# SchV1.net
KiCad netlist of a schematic drawn in Altium Designer
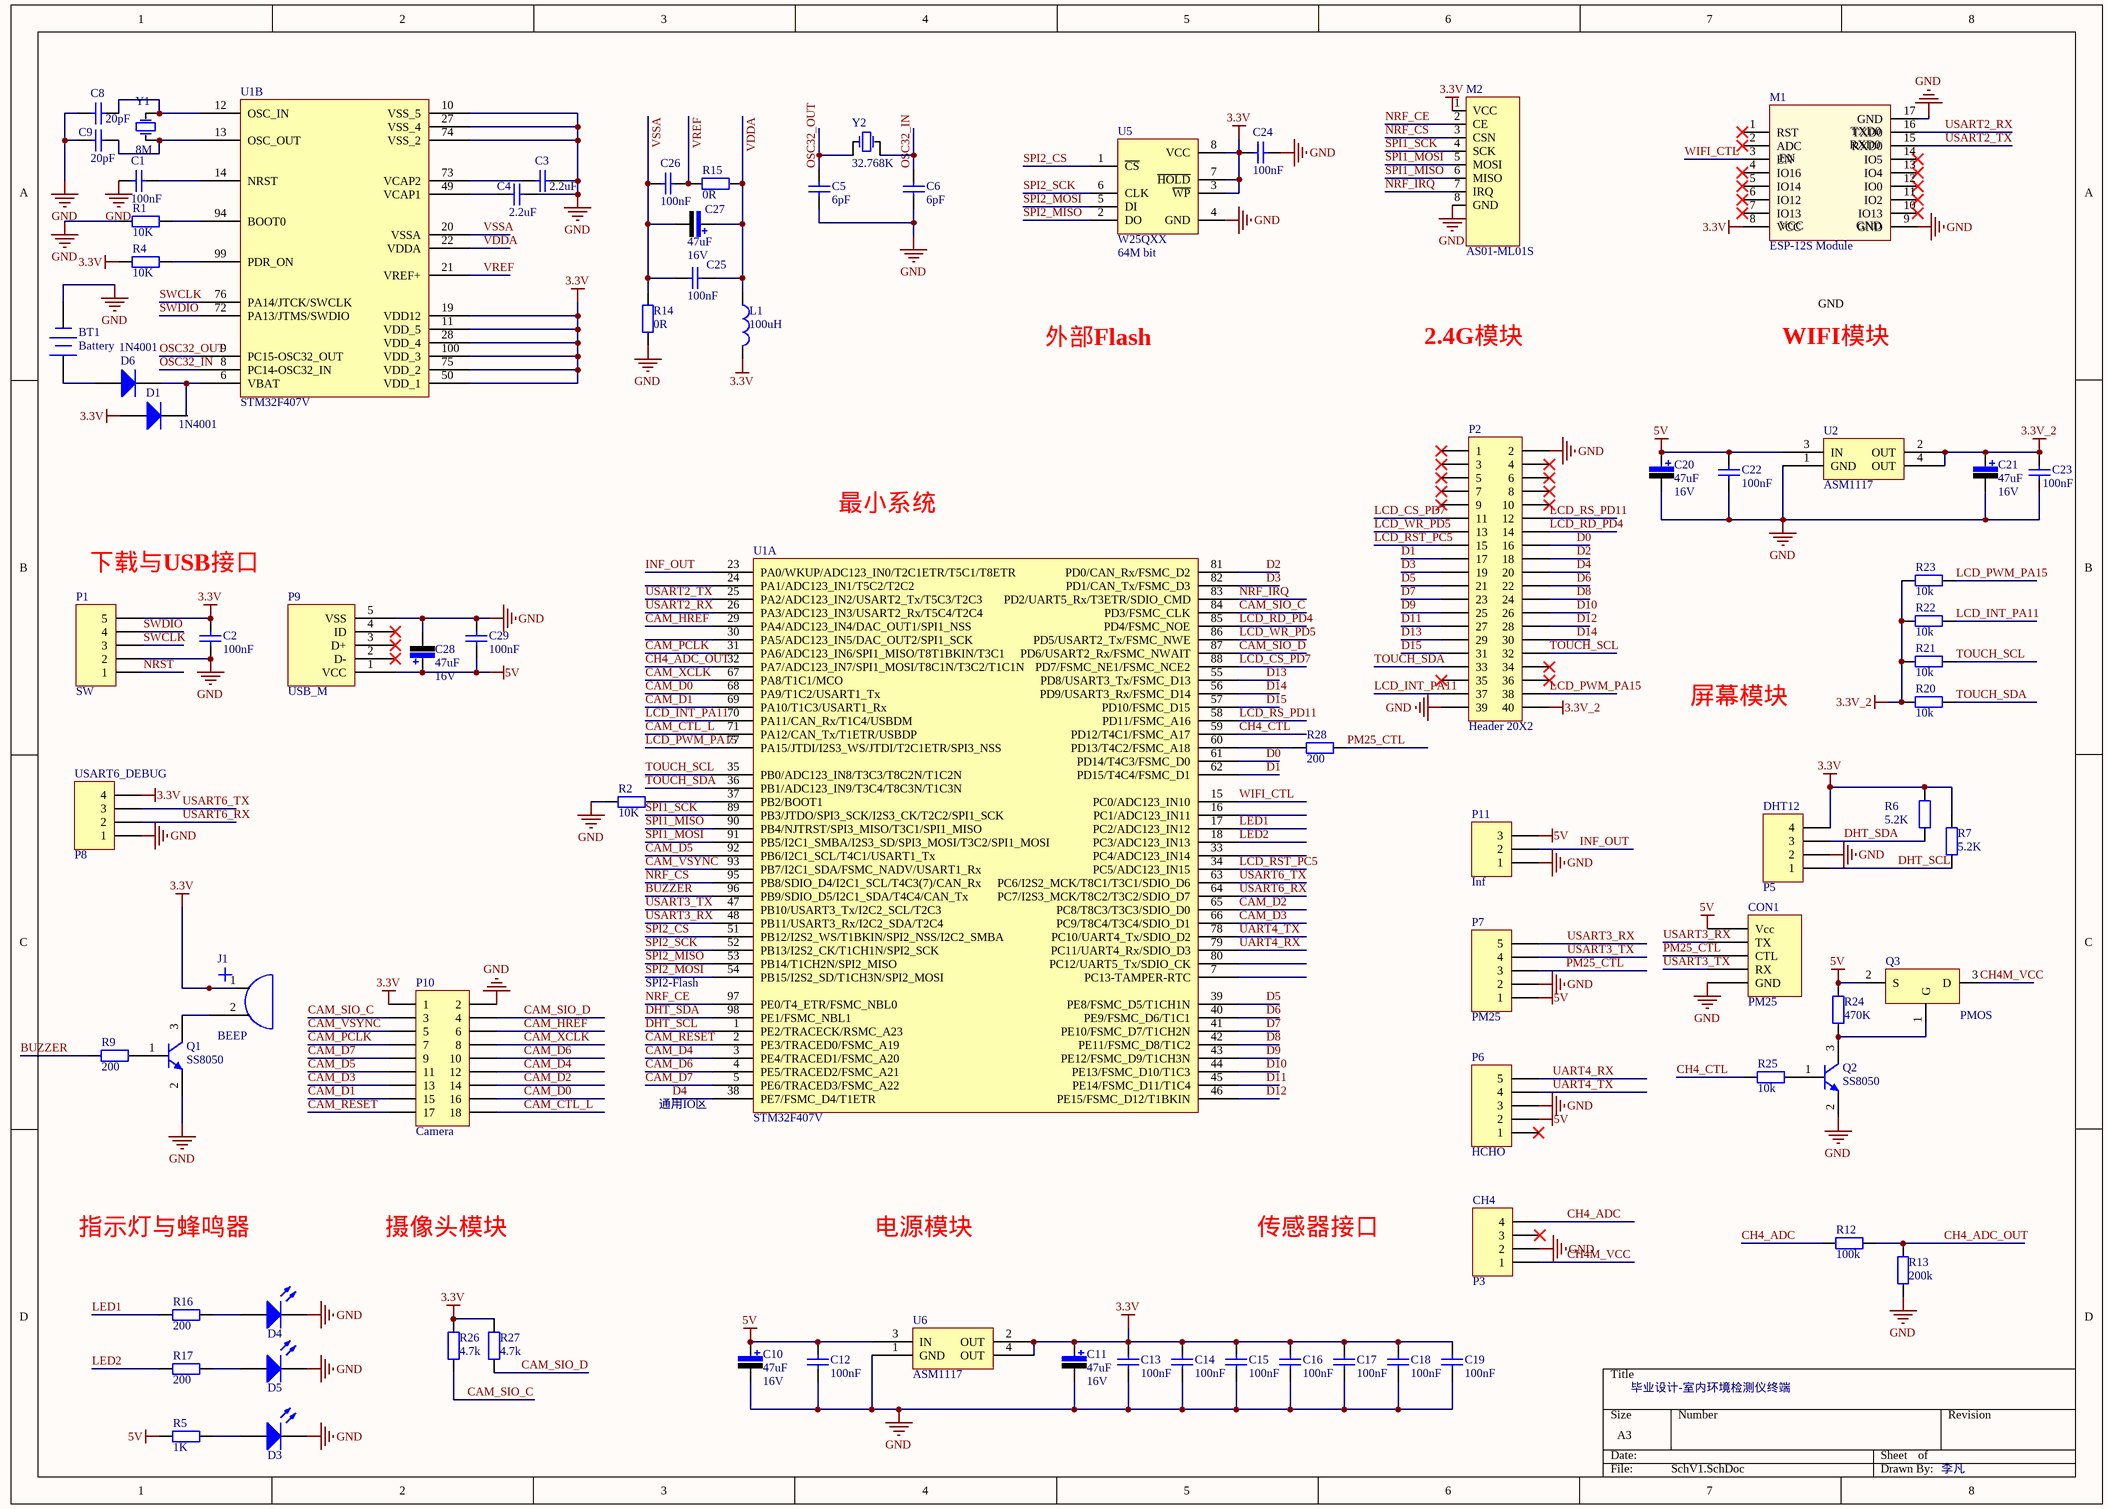
[diagram p0: SchV1.SchDoc]

(export (version "E")
  (design (tool "Eeschema 10.0.6"))
  (components
    (comp (ref "BT1")
      (value "Battery")
      (footprint "CR1220")
      (description "备份电池")
      (libsource (lib "Fszhang") (part "Battery"))
    )
    (comp (ref "C1")
      (value "100nF")
      (footprint "C-RAD-0603")
      (description "无极性电容")
      (fields (field (name "Comment") "Cap"))
      (libsource (lib "Fszhang") (part "Cap"))
    )
    (comp (ref "C2")
      (value "100nF")
      (footprint "C-RAD-0603")
      (description "无极性电容")
      (fields (field (name "Comment") "Cap"))
      (libsource (lib "Fszhang") (part "Cap"))
    )
    (comp (ref "C3")
      (value "2.2uF")
      (footprint "C-RAD-0603")
      (description "无极性电容")
      (fields (field (name "Comment") "Cap"))
      (libsource (lib "Fszhang") (part "Cap"))
    )
    (comp (ref "C4")
      (value "2.2uF")
      (footprint "C-RAD-0603")
      (description "无极性电容")
      (fields (field (name "Comment") "Cap"))
      (libsource (lib "Fszhang") (part "Cap"))
    )
    (comp (ref "C5")
      (value "6pF")
      (footprint "C-RAD-0603")
      (description "无极性电容")
      (fields (field (name "Comment") "Cap"))
      (libsource (lib "Fszhang") (part "Cap"))
    )
    (comp (ref "C6")
      (value "6pF")
      (footprint "C-RAD-0603")
      (description "无极性电容")
      (fields (field (name "Comment") "Cap"))
      (libsource (lib "Fszhang") (part "Cap"))
    )
    (comp (ref "C8")
      (value "20pF")
      (footprint "C-RAD-0603")
      (description "无极性电容")
      (fields (field (name "Comment") "Cap"))
      (libsource (lib "Fszhang") (part "Cap"))
    )
    (comp (ref "C9")
      (value "20pF")
      (footprint "C-RAD-0603")
      (description "无极性电容")
      (fields (field (name "Comment") "Cap"))
      (libsource (lib "Fszhang") (part "Cap"))
    )
    (comp (ref "C10")
      (value "47uF")
      (footprint "CAP-3528")
      (description "极性电解电容")
      (fields (field (name "VOL") "16V") (field (name "Comment") "Cap Pol"))
      (libsource (lib "") (part "Cap Pol_1"))
    )
    (comp (ref "C11")
      (value "47uF")
      (footprint "CAP-3528")
      (description "极性电解电容")
      (fields (field (name "VOL") "16V") (field (name "Comment") "Cap Pol"))
      (libsource (lib "") (part "Cap Pol_1"))
    )
    (comp (ref "C12")
      (value "100nF")
      (footprint "C-RAD-0603")
      (description "无极性电容")
      (fields (field (name "Comment") "Cap"))
      (libsource (lib "Fszhang") (part "Cap"))
    )
    (comp (ref "C13")
      (value "100nF")
      (footprint "C-RAD-0603")
      (description "无极性电容")
      (fields (field (name "Comment") "Cap"))
      (libsource (lib "Fszhang") (part "Cap"))
    )
    (comp (ref "C14")
      (value "100nF")
      (footprint "C-RAD-0603")
      (description "无极性电容")
      (fields (field (name "Comment") "Cap"))
      (libsource (lib "Fszhang") (part "Cap"))
    )
    (comp (ref "C15")
      (value "100nF")
      (footprint "C-RAD-0603")
      (description "无极性电容")
      (fields (field (name "Comment") "Cap"))
      (libsource (lib "Fszhang") (part "Cap"))
    )
    (comp (ref "C16")
      (value "100nF")
      (footprint "C-RAD-0603")
      (description "无极性电容")
      (fields (field (name "Comment") "Cap"))
      (libsource (lib "Fszhang") (part "Cap"))
    )
    (comp (ref "C17")
      (value "100nF")
      (footprint "C-RAD-0603")
      (description "无极性电容")
      (fields (field (name "Comment") "Cap"))
      (libsource (lib "Fszhang") (part "Cap"))
    )
    (comp (ref "C18")
      (value "100nF")
      (footprint "C-RAD-0603")
      (description "无极性电容")
      (fields (field (name "Comment") "Cap"))
      (libsource (lib "Fszhang") (part "Cap"))
    )
    (comp (ref "C19")
      (value "100nF")
      (footprint "C-RAD-0603")
      (description "无极性电容")
      (fields (field (name "Comment") "Cap"))
      (libsource (lib "Fszhang") (part "Cap"))
    )
    (comp (ref "C20")
      (value "47uF")
      (footprint "CAP-3528")
      (description "极性电解电容")
      (fields (field (name "VOL") "16V") (field (name "Comment") "Cap Pol"))
      (libsource (lib "") (part "Cap Pol_1"))
    )
    (comp (ref "C21")
      (value "47uF")
      (footprint "CAP-3528")
      (description "极性电解电容")
      (fields (field (name "VOL") "16V") (field (name "Comment") "Cap Pol"))
      (libsource (lib "") (part "Cap Pol_1"))
    )
    (comp (ref "C22")
      (value "100nF")
      (footprint "C-RAD-0603")
      (description "无极性电容")
      (fields (field (name "Comment") "Cap"))
      (libsource (lib "Fszhang") (part "Cap"))
    )
    (comp (ref "C23")
      (value "100nF")
      (footprint "C-RAD-0603")
      (description "无极性电容")
      (fields (field (name "Comment") "Cap"))
      (libsource (lib "Fszhang") (part "Cap"))
    )
    (comp (ref "C24")
      (value "100nF")
      (footprint "C-RAD-0603")
      (description "无极性电容")
      (fields (field (name "Comment") "Cap"))
      (libsource (lib "Fszhang") (part "Cap"))
    )
    (comp (ref "C25")
      (value "100nF")
      (footprint "C-RAD-0603")
      (description "无极性电容")
      (fields (field (name "Comment") "Cap"))
      (libsource (lib "Fszhang") (part "Cap"))
    )
    (comp (ref "C26")
      (value "100nF")
      (footprint "C-RAD-0603")
      (description "无极性电容")
      (fields (field (name "Comment") "Cap"))
      (libsource (lib "Fszhang") (part "Cap"))
    )
    (comp (ref "C27")
      (value "47uF")
      (footprint "CAP-3528")
      (description "极性电解电容")
      (fields (field (name "VOL") "16V") (field (name "Comment") "Cap Pol"))
      (libsource (lib "Fszhang") (part "Cap Pol"))
    )
    (comp (ref "C28")
      (value "47uF")
      (footprint "CAP-3528")
      (description "极性电解电容")
      (fields (field (name "VOL") "16V") (field (name "Comment") "Cap Pol"))
      (libsource (lib "") (part "Cap Pol_2"))
    )
    (comp (ref "C29")
      (value "100nF")
      (footprint "C-RAD-0603")
      (description "无极性电容")
      (fields (field (name "Comment") "Cap"))
      (libsource (lib "Fszhang") (part "Cap"))
    )
    (comp (ref "CON1") (value "PM25") (libsource (lib "Schlib") (part "USART_sensor")))
    (comp (ref "D1")
      (value "Diode")
      (footprint "DIODE-1206")
      (description "二极管")
      (fields (field (name "TYPE") "1N4001"))
      (libsource (lib "Fszhang") (part "Diode"))
    )
    (comp (ref "D3")
      (value "LED0")
      (footprint "LED_0805")
      (description "发光二极管")
      (libsource (lib "Fszhang") (part "LED0"))
    )
    (comp (ref "D4")
      (value "LED0")
      (footprint "LED_0805")
      (description "发光二极管")
      (libsource (lib "Fszhang") (part "LED0"))
    )
    (comp (ref "D5")
      (value "LED0")
      (footprint "LED_0805")
      (description "发光二极管")
      (libsource (lib "Fszhang") (part "LED0"))
    )
    (comp (ref "D6")
      (value "Diode")
      (footprint "DIODE-1206")
      (description "二极管")
      (fields (field (name "TYPE") "1N4001"))
      (libsource (lib "Fszhang") (part "Diode"))
    )
    (comp (ref "J1")
      (value "BEEP")
      (footprint "Beep")
      (description "蜂鸣器")
      (libsource (lib "Fszhang") (part "BEEP"))
    )
    (comp (ref "L1")
      (value "100uH")
      (footprint "0805-1")
      (description "电感")
      (fields (field (name "Comment") "Inductor"))
      (libsource (lib "Fszhang") (part "Inductor"))
    )
    (comp (ref "M1")
      (value "ESP-12S Module")
      (footprint "ESP-12S Module")
      (libsource (lib "ESP-12S Module") (part "ESP-12S Module"))
    )
    (comp (ref "M2")
      (value "AS01-ML01S")
      (footprint "FanliPcbLib:AS01-ML01S")
      (description "贴片2.4G模块")
      (libsource (lib "Schlib") (part "AS01-ML01S"))
    )
    (comp (ref "P1")
      (value "SW")
      (footprint "FanliPcbLib:7-Header_7mm")
      (description "Header, 5-Pin")
      (libsource (lib "Miscellaneous Connectors") (part "Header 5"))
    )
    (comp (ref "P2")
      (value "Header 20X2")
      (footprint "HDR2X20")
      (description "Header, 20-Pin, Dual row")
      (libsource (lib "Miscellaneous Connectors") (part "Header 20X2"))
    )
    (comp (ref "P3")
      (value "CH4")
      (footprint "HDR4X1_A")
      (description "接插件")
      (libsource (lib "Fszhang") (part "Header 4"))
    )
    (comp (ref "P5")
      (value "DHT12")
      (footprint "HDR4X1_A")
      (description "接插件")
      (libsource (lib "Fszhang") (part "Header 4"))
    )
    (comp (ref "P6")
      (value "HCHO")
      (footprint "7-Header_7mm")
      (description "Header, 5-Pin")
      (libsource (lib "Miscellaneous Connectors") (part "Header 5"))
    )
    (comp (ref "P7")
      (value "PM25")
      (footprint "7-Header_7mm")
      (description "Header, 5-Pin")
      (libsource (lib "Miscellaneous Connectors") (part "Header 5"))
    )
    (comp (ref "P8")
      (value "USART6_DEBUG")
      (footprint "HDR4X1_A")
      (description "接插件")
      (libsource (lib "Fszhang") (part "Header 4"))
    )
    (comp (ref "P9")
      (value "USB_M")
      (footprint "USB_MICRO")
      (description "MicroUSB接口")
      (libsource (lib "Fszhang") (part "USB_M"))
    )
    (comp (ref "P10")
      (value "Camera")
      (footprint "HDR2X9")
      (description "Header, 9-Pin, Dual row")
      (libsource (lib "Miscellaneous Connectors") (part "Header 9X2"))
    )
    (comp (ref "P11")
      (value "Inf")
      (footprint "HDR1X3")
      (description "Header, 3-Pin")
      (libsource (lib "Miscellaneous Connectors") (part "Header 3"))
    )
    (comp (ref "Q1")
      (value "SS8050")
      (footprint "SOT-23")
      (description "NPN贴片三极管")
      (libsource (lib "Fszhang") (part "SS8050"))
    )
    (comp (ref "Q2")
      (value "SS8050")
      (footprint "SOT-23")
      (description "NPN贴片三极管")
      (libsource (lib "Fszhang") (part "SS8050"))
    )
    (comp (ref "Q3") (value "PMOS") (footprint "FanliPcbLib:SOT-23") (libsource (lib "Schlib") (part "PMOS")))
    (comp (ref "R1")
      (value "10K")
      (footprint "0603-1")
      (description "贴片电阻")
      (fields (field (name "Comment") "Res1"))
      (libsource (lib "") (part "Res1_2"))
    )
    (comp (ref "R2")
      (value "10K")
      (footprint "0603-1")
      (description "贴片电阻")
      (fields (field (name "Comment") "Res1"))
      (libsource (lib "") (part "Res1_2"))
    )
    (comp (ref "R4")
      (value "10K")
      (footprint "0603-1")
      (description "贴片电阻")
      (fields (field (name "Comment") "Res1"))
      (libsource (lib "") (part "Res1_2"))
    )
    (comp (ref "R5")
      (value "1K")
      (footprint "0603-1")
      (description "贴片电阻")
      (fields (field (name "Comment") "Res1"))
      (libsource (lib "Fszhang") (part "Res1"))
    )
    (comp (ref "R6")
      (value "5.2K")
      (footprint "0603-1")
      (description "贴片电阻")
      (fields (field (name "Comment") "Res1"))
      (libsource (lib "") (part "Res1_1"))
    )
    (comp (ref "R7")
      (value "5.2K")
      (footprint "0603-1")
      (description "贴片电阻")
      (fields (field (name "Comment") "Res1"))
      (libsource (lib "") (part "Res1_1"))
    )
    (comp (ref "R9")
      (value "200")
      (footprint "0603-1")
      (description "贴片电阻")
      (fields (field (name "Comment") "Res1"))
      (libsource (lib "Fszhang") (part "Res1"))
    )
    (comp (ref "R12")
      (value "100k")
      (footprint "0603-1")
      (description "贴片电阻")
      (fields (field (name "Comment") "Res1"))
      (libsource (lib "") (part "Res1_2"))
    )
    (comp (ref "R13")
      (value "200k")
      (footprint "0603-1")
      (description "贴片电阻")
      (fields (field (name "Comment") "Res1"))
      (libsource (lib "") (part "Res1_1"))
    )
    (comp (ref "R14")
      (value "0R")
      (footprint "0603-1")
      (description "贴片电阻")
      (fields (field (name "Comment") "Res1"))
      (libsource (lib "") (part "Res1_1"))
    )
    (comp (ref "R15")
      (value "0R")
      (footprint "0603-1")
      (description "贴片电阻")
      (fields (field (name "Comment") "Res1"))
      (libsource (lib "Fszhang") (part "Res1"))
    )
    (comp (ref "R16")
      (value "200")
      (footprint "0603-1")
      (description "贴片电阻")
      (fields (field (name "Comment") "Res1"))
      (libsource (lib "Fszhang") (part "Res1"))
    )
    (comp (ref "R17")
      (value "200")
      (footprint "0603-1")
      (description "贴片电阻")
      (fields (field (name "Comment") "Res1"))
      (libsource (lib "Fszhang") (part "Res1"))
    )
    (comp (ref "R20")
      (value "10k")
      (footprint "0603-1")
      (description "贴片电阻")
      (fields (field (name "Comment") "Res1"))
      (libsource (lib "Fszhang") (part "Res1"))
    )
    (comp (ref "R21")
      (value "10k")
      (footprint "0603-1")
      (description "贴片电阻")
      (fields (field (name "Comment") "Res1"))
      (libsource (lib "Fszhang") (part "Res1"))
    )
    (comp (ref "R22")
      (value "10k")
      (footprint "0603-1")
      (description "贴片电阻")
      (fields (field (name "Comment") "Res1"))
      (libsource (lib "Fszhang") (part "Res1"))
    )
    (comp (ref "R23")
      (value "10k")
      (footprint "0603-1")
      (description "贴片电阻")
      (fields (field (name "Comment") "Res1"))
      (libsource (lib "Fszhang") (part "Res1"))
    )
    (comp (ref "R24")
      (value "470K")
      (footprint "0603-1")
      (description "贴片电阻")
      (fields (field (name "Comment") "Res1"))
      (libsource (lib "") (part "Res1_1"))
    )
    (comp (ref "R25")
      (value "10k")
      (footprint "0603-1")
      (description "贴片电阻")
      (fields (field (name "Comment") "Res1"))
      (libsource (lib "Fszhang") (part "Res1"))
    )
    (comp (ref "R26")
      (value "4.7k")
      (footprint "0603-1")
      (description "贴片电阻")
      (fields (field (name "Comment") "Res1"))
      (libsource (lib "") (part "Res1_1"))
    )
    (comp (ref "R27")
      (value "4.7k")
      (footprint "0603-1")
      (description "贴片电阻")
      (fields (field (name "Comment") "Res1"))
      (libsource (lib "") (part "Res1_3"))
    )
    (comp (ref "R28")
      (value "200")
      (footprint "0603-1")
      (description "贴片电阻")
      (fields (field (name "Comment") "Res1"))
      (libsource (lib "") (part "Res1_2"))
    )
    (comp (ref "U1")
      (value "STM32F407V")
      (footprint "LQFP-100_M")
      (description "STM32单片机100引脚")
      (libsource (lib "") (part "STM32F407V_1"))
    )
    (comp (ref "U2")
      (value "ASM1117")
      (footprint "SOT-223")
      (description "3.3V稳压芯片")
      (libsource (lib "Fszhang") (part "ASM1117"))
    )
    (comp (ref "U5")
      (value "W25QXX")
      (footprint "SOIC8_W")
      (description "SPI FLASH")
      (fields (field (name "MEMORY") "64M bit"))
      (libsource (lib "Fszhang") (part "W25QXX"))
    )
    (comp (ref "U6")
      (value "ASM1117")
      (footprint "SOT-223")
      (description "3.3V稳压芯片")
      (libsource (lib "Fszhang") (part "ASM1117"))
    )
    (comp (ref "Y1")
      (value "8M")
      (footprint "X-SM49")
      (description "晶振")
      (fields (field (name "Comment") "XTAL"))
      (libsource (lib "Fszhang") (part "XTAL"))
    )
    (comp (ref "Y2")
      (value "32.768K")
      (footprint "MC-306")
      (description "晶振")
      (fields (field (name "Comment") "XTAL"))
      (libsource (lib "Fszhang") (part "XTAL"))
    )
  )
  (nets
    (net (code "1") (name "/BUZZER") (class "Default")
      (node (ref "R9") (pin "2") (pinfunction "2_2") (pintype "passive"))
      (node (ref "U1") (pin "96") (pinfunction "PB9/SDIO_D5/I2C1_SDA/T4C4/CAN_Tx_96") (pintype "passive"))
    )
    (net (code "2") (name "/CAM_CTL_L") (class "Default")
      (node (ref "P10") (pin "18") (pinfunction "18_18") (pintype "passive"))
      (node (ref "U1") (pin "71") (pinfunction "PA12/CAN_Tx/T1ETR/USBDP_71") (pintype "passive"))
    )
    (net (code "3") (name "/CAM_D0") (class "Default")
      (node (ref "P10") (pin "16") (pinfunction "16_16") (pintype "passive"))
      (node (ref "U1") (pin "68") (pinfunction "PA9/T1C2/USART1_Tx_68") (pintype "passive"))
    )
    (net (code "4") (name "/CAM_D1") (class "Default")
      (node (ref "P10") (pin "15") (pinfunction "15_15") (pintype "passive"))
      (node (ref "U1") (pin "69") (pinfunction "PA10/T1C3/USART1_Rx_69") (pintype "passive"))
    )
    (net (code "5") (name "/CAM_D2") (class "Default")
      (node (ref "P10") (pin "14") (pinfunction "14_14") (pintype "passive"))
      (node (ref "U1") (pin "65") (pinfunction "PC8/T8C3/T3C3/SDIO_D0_65") (pintype "passive"))
    )
    (net (code "6") (name "/CAM_D3") (class "Default")
      (node (ref "P10") (pin "13") (pinfunction "13_13") (pintype "passive"))
      (node (ref "U1") (pin "66") (pinfunction "PC9/T8C4/T3C4/SDIO_D1_66") (pintype "passive"))
    )
    (net (code "7") (name "/CAM_D4") (class "Default")
      (node (ref "P10") (pin "12") (pinfunction "12_12") (pintype "passive"))
      (node (ref "U1") (pin "3") (pinfunction "PE4/TRACED1/FSMC_A20_3") (pintype "passive"))
    )
    (net (code "8") (name "/CAM_D5") (class "Default")
      (node (ref "P10") (pin "11") (pinfunction "11_11") (pintype "passive"))
      (node (ref "U1") (pin "92") (pinfunction "PB6/I2C1_SCL/T4C1/USART1_Tx_92") (pintype "passive"))
    )
    (net (code "9") (name "/CAM_D6") (class "Default")
      (node (ref "P10") (pin "10") (pinfunction "10_10") (pintype "passive"))
      (node (ref "U1") (pin "4") (pinfunction "PE5/TRACED2/FSMC_A21_4") (pintype "passive"))
    )
    (net (code "10") (name "/CAM_D7") (class "Default")
      (node (ref "P10") (pin "9") (pinfunction "9_9") (pintype "passive"))
      (node (ref "U1") (pin "5") (pinfunction "PE6/TRACED3/FSMC_A22_5") (pintype "passive"))
    )
    (net (code "11") (name "/CAM_HREF") (class "Default")
      (node (ref "P10") (pin "6") (pinfunction "6_6") (pintype "passive"))
      (node (ref "U1") (pin "29") (pinfunction "PA4/ADC123_IN4/DAC_OUT1/SPI1_NSS_29") (pintype "passive"))
    )
    (net (code "12") (name "/CAM_PCLK") (class "Default")
      (node (ref "P10") (pin "7") (pinfunction "7_7") (pintype "passive"))
      (node (ref "U1") (pin "31") (pinfunction "PA6/ADC123_IN6/SPI1_MISO/T8T1BKIN/T3C1_31") (pintype "passive"))
    )
    (net (code "13") (name "/CAM_RESET") (class "Default")
      (node (ref "P10") (pin "17") (pinfunction "17_17") (pintype "passive"))
      (node (ref "U1") (pin "2") (pinfunction "PE3/TRACED0/FSMC_A19_2") (pintype "passive"))
    )
    (net (code "14") (name "/CAM_SIO_C") (class "Default")
      (node (ref "P10") (pin "3") (pinfunction "3_3") (pintype "passive"))
      (node (ref "R26") (pin "1") (pinfunction "1_1") (pintype "passive"))
      (node (ref "U1") (pin "84") (pinfunction "PD3/FSMC_CLK_84") (pintype "passive"))
    )
    (net (code "15") (name "/CAM_SIO_D") (class "Default")
      (node (ref "P10") (pin "4") (pinfunction "4_4") (pintype "passive"))
      (node (ref "R27") (pin "2") (pinfunction "2_2") (pintype "passive"))
      (node (ref "U1") (pin "87") (pinfunction "PD6/USART2_Rx/FSMC_NWAIT_87") (pintype "passive"))
    )
    (net (code "16") (name "/CAM_VSYNC") (class "Default")
      (node (ref "P10") (pin "5") (pinfunction "5_5") (pintype "passive"))
      (node (ref "U1") (pin "93") (pinfunction "PB7/I2C1_SDA/FSMC_NADV/USART1_Rx_93") (pintype "passive"))
    )
    (net (code "17") (name "/CAM_XCLK") (class "Default")
      (node (ref "P10") (pin "8") (pinfunction "8_8") (pintype "passive"))
      (node (ref "U1") (pin "67") (pinfunction "PA8/T1C1/MCO_67") (pintype "passive"))
    )
    (net (code "18") (name "/CH4M_VCC") (class "Default")
      (node (ref "P3") (pin "1") (pinfunction "1_1") (pintype "passive"))
      (node (ref "Q3") (pin "3") (pinfunction "D_3") (pintype "passive"))
    )
    (net (code "19") (name "/CH4_ADC") (class "Default")
      (node (ref "P3") (pin "4") (pinfunction "4_4") (pintype "passive"))
      (node (ref "R12") (pin "1") (pinfunction "1_1") (pintype "passive"))
    )
    (net (code "20") (name "/CH4_ADC_OUT") (class "Default")
      (node (ref "R12") (pin "2") (pinfunction "2_2") (pintype "passive"))
      (node (ref "R13") (pin "2") (pinfunction "2_2") (pintype "passive"))
      (node (ref "U1") (pin "32") (pinfunction "PA7/ADC123_IN7/SPI1_MOSI/T8C1N/T3C2/T1C1N_32") (pintype "passive"))
    )
    (net (code "21") (name "/CH4_CTL") (class "Default")
      (node (ref "R25") (pin "2") (pinfunction "2_2") (pintype "passive"))
      (node (ref "U1") (pin "59") (pinfunction "PD12/T4C1/FSMC_A17_59") (pintype "passive"))
    )
    (net (code "22") (name "/D0") (class "Default")
      (node (ref "P2") (pin "16") (pinfunction "16_16") (pintype "passive"))
      (node (ref "U1") (pin "61") (pinfunction "PD14/T4C3/FSMC_D0_61") (pintype "passive"))
    )
    (net (code "23") (name "/D1") (class "Default")
      (node (ref "P2") (pin "17") (pinfunction "17_17") (pintype "passive"))
      (node (ref "U1") (pin "62") (pinfunction "PD15/T4C4/FSMC_D1_62") (pintype "passive"))
    )
    (net (code "24") (name "/D2") (class "Default")
      (node (ref "P2") (pin "18") (pinfunction "18_18") (pintype "passive"))
      (node (ref "U1") (pin "81") (pinfunction "PD0/CAN_Rx/FSMC_D2_81") (pintype "passive"))
    )
    (net (code "25") (name "/D3") (class "Default")
      (node (ref "P2") (pin "19") (pinfunction "19_19") (pintype "passive"))
      (node (ref "U1") (pin "82") (pinfunction "PD1/CAN_Tx/FSMC_D3_82") (pintype "passive"))
    )
    (net (code "26") (name "/D4") (class "Default")
      (node (ref "P2") (pin "20") (pinfunction "20_20") (pintype "passive"))
      (node (ref "U1") (pin "38") (pinfunction "PE7/FSMC_D4/T1ETR_38") (pintype "passive"))
    )
    (net (code "27") (name "/D5") (class "Default")
      (node (ref "P2") (pin "21") (pinfunction "21_21") (pintype "passive"))
      (node (ref "U1") (pin "39") (pinfunction "PE8/FSMC_D5/T1CH1N_39") (pintype "passive"))
    )
    (net (code "28") (name "/D6") (class "Default")
      (node (ref "P2") (pin "22") (pinfunction "22_22") (pintype "passive"))
      (node (ref "U1") (pin "40") (pinfunction "PE9/FSMC_D6/T1C1_40") (pintype "passive"))
    )
    (net (code "29") (name "/D7") (class "Default")
      (node (ref "P2") (pin "23") (pinfunction "23_23") (pintype "passive"))
      (node (ref "U1") (pin "41") (pinfunction "PE10/FSMC_D7/T1CH2N_41") (pintype "passive"))
    )
    (net (code "30") (name "/D8") (class "Default")
      (node (ref "P2") (pin "24") (pinfunction "24_24") (pintype "passive"))
      (node (ref "U1") (pin "42") (pinfunction "PE11/FSMC_D8/T1C2_42") (pintype "passive"))
    )
    (net (code "31") (name "/D9") (class "Default")
      (node (ref "P2") (pin "25") (pinfunction "25_25") (pintype "passive"))
      (node (ref "U1") (pin "43") (pinfunction "PE12/FSMC_D9/T1CH3N_43") (pintype "passive"))
    )
    (net (code "32") (name "/D10") (class "Default")
      (node (ref "P2") (pin "26") (pinfunction "26_26") (pintype "passive"))
      (node (ref "U1") (pin "44") (pinfunction "PE13/FSMC_D10/T1C3_44") (pintype "passive"))
    )
    (net (code "33") (name "/D11") (class "Default")
      (node (ref "P2") (pin "27") (pinfunction "27_27") (pintype "passive"))
      (node (ref "U1") (pin "45") (pinfunction "PE14/FSMC_D11/T1C4_45") (pintype "passive"))
    )
    (net (code "34") (name "/D12") (class "Default")
      (node (ref "P2") (pin "28") (pinfunction "28_28") (pintype "passive"))
      (node (ref "U1") (pin "46") (pinfunction "PE15/FSMC_D12/T1BKIN_46") (pintype "passive"))
    )
    (net (code "35") (name "/D13") (class "Default")
      (node (ref "P2") (pin "29") (pinfunction "29_29") (pintype "passive"))
      (node (ref "U1") (pin "55") (pinfunction "PD8/USART3_Tx/FSMC_D13_55") (pintype "passive"))
    )
    (net (code "36") (name "/D14") (class "Default")
      (node (ref "P2") (pin "30") (pinfunction "30_30") (pintype "passive"))
      (node (ref "U1") (pin "56") (pinfunction "PD9/USART3_Rx/FSMC_D14_56") (pintype "passive"))
    )
    (net (code "37") (name "/D15") (class "Default")
      (node (ref "P2") (pin "31") (pinfunction "31_31") (pintype "passive"))
      (node (ref "U1") (pin "57") (pinfunction "PD10/FSMC_D15_57") (pintype "passive"))
    )
    (net (code "38") (name "/DHT_SCL") (class "Default")
      (node (ref "P5") (pin "1") (pinfunction "1_1") (pintype "passive"))
      (node (ref "R7") (pin "1") (pinfunction "1_1") (pintype "passive"))
      (node (ref "U1") (pin "1") (pinfunction "PE2/TRACECK/RSMC_A23_1") (pintype "passive"))
    )
    (net (code "39") (name "/DHT_SDA") (class "Default")
      (node (ref "P5") (pin "3") (pinfunction "3_3") (pintype "passive"))
      (node (ref "R6") (pin "1") (pinfunction "1_1") (pintype "passive"))
      (node (ref "U1") (pin "98") (pinfunction "PE1/FSMC_NBL1_98") (pintype "passive"))
    )
    (net (code "40") (name "/INF_OUT") (class "Default")
      (node (ref "P11") (pin "2") (pinfunction "2_2") (pintype "passive"))
      (node (ref "U1") (pin "23") (pinfunction "PA0/WKUP/ADC123_IN0/T2C1ETR/T5C1/T8ETR_23") (pintype "passive"))
    )
    (net (code "41") (name "/LCD_CS_PD7") (class "Default")
      (node (ref "P2") (pin "11") (pinfunction "11_11") (pintype "passive"))
      (node (ref "U1") (pin "88") (pinfunction "PD7/FSMC_NE1/FSMC_NCE2_88") (pintype "passive"))
    )
    (net (code "42") (name "/LCD_INT_PA11") (class "Default")
      (node (ref "P2") (pin "37") (pinfunction "37_37") (pintype "passive"))
      (node (ref "R22") (pin "1") (pinfunction "1_1") (pintype "passive"))
      (node (ref "U1") (pin "70") (pinfunction "PA11/CAN_Rx/T1C4/USBDM_70") (pintype "passive"))
    )
    (net (code "43") (name "/LCD_PWM_PA15") (class "Default")
      (node (ref "P2") (pin "38") (pinfunction "38_38") (pintype "passive"))
      (node (ref "R23") (pin "1") (pinfunction "1_1") (pintype "passive"))
      (node (ref "U1") (pin "77") (pinfunction "PA15/JTDI/I2S3_WS/JTDI/T2C1ETR/SPI3_NSS_77") (pintype "passive"))
    )
    (net (code "44") (name "/LCD_RD_PD4") (class "Default")
      (node (ref "P2") (pin "14") (pinfunction "14_14") (pintype "passive"))
      (node (ref "U1") (pin "85") (pinfunction "PD4/FSMC_NOE_85") (pintype "passive"))
    )
    (net (code "45") (name "/LCD_RST_PC5") (class "Default")
      (node (ref "P2") (pin "15") (pinfunction "15_15") (pintype "passive"))
      (node (ref "U1") (pin "34") (pinfunction "PC5/ADC123_IN15_34") (pintype "passive"))
    )
    (net (code "46") (name "/LCD_RS_PD11") (class "Default")
      (node (ref "P2") (pin "12") (pinfunction "12_12") (pintype "passive"))
      (node (ref "U1") (pin "58") (pinfunction "PD11/FSMC_A16_58") (pintype "passive"))
    )
    (net (code "47") (name "/LCD_WR_PD5") (class "Default")
      (node (ref "P2") (pin "13") (pinfunction "13_13") (pintype "passive"))
      (node (ref "U1") (pin "86") (pinfunction "PD5/USART2_Tx/FSMC_NWE_86") (pintype "passive"))
    )
    (net (code "48") (name "/LED1") (class "Default")
      (node (ref "R16") (pin "2") (pinfunction "2_2") (pintype "passive"))
      (node (ref "U1") (pin "17") (pinfunction "PC2/ADC123_IN12_17") (pintype "passive"))
    )
    (net (code "49") (name "/LED2") (class "Default")
      (node (ref "R17") (pin "2") (pinfunction "2_2") (pintype "passive"))
      (node (ref "U1") (pin "18") (pinfunction "PC3/ADC123_IN13_18") (pintype "passive"))
    )
    (net (code "50") (name "/NRF_CE") (class "Default")
      (node (ref "M2") (pin "2") (pinfunction "CE_2") (pintype "passive"))
      (node (ref "U1") (pin "97") (pinfunction "PE0/T4_ETR/FSMC_NBL0_97") (pintype "passive"))
    )
    (net (code "51") (name "/NRF_CS") (class "Default")
      (node (ref "M2") (pin "3") (pinfunction "CSN_3") (pintype "passive"))
      (node (ref "U1") (pin "95") (pinfunction "PB8/SDIO_D4/I2C1_SCL/T4C3(7)/CAN_Rx_95") (pintype "passive"))
    )
    (net (code "52") (name "/NRF_IRQ") (class "Default")
      (node (ref "M2") (pin "7") (pinfunction "IRQ_7") (pintype "passive"))
      (node (ref "U1") (pin "83") (pinfunction "PD2/UART5_Rx/T3ETR/SDIO_CMD_83") (pintype "passive"))
    )
    (net (code "53") (name "/NRST") (class "Default")
      (node (ref "P1") (pin "1") (pinfunction "1_1") (pintype "passive"))
    )
    (net (code "54") (name "/OSC32_IN") (class "Default")
      (node (ref "C6") (pin "2") (pinfunction "2_2") (pintype "passive"))
      (node (ref "U1") (pin "8") (pinfunction "PC14-OSC32_IN_8") (pintype "passive"))
      (node (ref "Y2") (pin "2") (pinfunction "OSC2_2") (pintype "passive"))
    )
    (net (code "55") (name "/OSC32_OUT") (class "Default")
      (node (ref "C5") (pin "2") (pinfunction "2_2") (pintype "passive"))
      (node (ref "U1") (pin "9") (pinfunction "PC15-OSC32_OUT_9") (pintype "passive"))
      (node (ref "Y2") (pin "1") (pinfunction "OSC1_1") (pintype "passive"))
    )
    (net (code "56") (name "/PM25_CTL") (class "Default")
      (node (ref "CON1") (pin "2") (pinfunction "CTL_2") (pintype "passive"))
      (node (ref "P7") (pin "3") (pinfunction "3_3") (pintype "passive"))
      (node (ref "R28") (pin "2") (pinfunction "2_2") (pintype "passive"))
    )
    (net (code "57") (name "/SPI1_MISO") (class "Default")
      (node (ref "M2") (pin "6") (pinfunction "MISO_6") (pintype "passive"))
      (node (ref "U1") (pin "90") (pinfunction "PB4/NJTRST/SPI3_MISO/T3C1/SPI1_MISO_90") (pintype "passive"))
    )
    (net (code "58") (name "/SPI1_MOSI") (class "Default")
      (node (ref "M2") (pin "5") (pinfunction "MOSI_5") (pintype "passive"))
      (node (ref "U1") (pin "91") (pinfunction "PB5/I2C1_SMBA/I2S3_SD/SPI3_MOSI/T3C2/SPI1_MOSI_91") (pintype "passive"))
    )
    (net (code "59") (name "/SPI1_SCK") (class "Default")
      (node (ref "M2") (pin "4") (pinfunction "SCK_4") (pintype "passive"))
      (node (ref "U1") (pin "89") (pinfunction "PB3/JTDO/SPI3_SCK/I2S3_CK/T2C2/SPI1_SCK_89") (pintype "passive"))
    )
    (net (code "60") (name "/SPI2_CS") (class "Default")
      (node (ref "U1") (pin "51") (pinfunction "PB12/I2S2_WS/T1BKIN/SPI2_NSS/I2C2_SMBA_51") (pintype "passive"))
      (node (ref "U5") (pin "1") (pinfunction "~{CS}_1") (pintype "passive"))
    )
    (net (code "61") (name "/SPI2_MISO") (class "Default")
      (node (ref "U1") (pin "53") (pinfunction "PB14/T1CH2N/SPI2_MISO_53") (pintype "passive"))
      (node (ref "U5") (pin "2") (pinfunction "DO_2") (pintype "passive"))
    )
    (net (code "62") (name "/SPI2_MOSI") (class "Default")
      (node (ref "U1") (pin "54") (pinfunction "PB15/I2S2_SD/T1CH3N/SPI2_MOSI_54") (pintype "passive"))
      (node (ref "U5") (pin "5") (pinfunction "DI_5") (pintype "passive"))
    )
    (net (code "63") (name "/SPI2_SCK") (class "Default")
      (node (ref "U1") (pin "52") (pinfunction "PB13/I2S2_CK/T1CH1N/SPI2_SCK_52") (pintype "passive"))
      (node (ref "U5") (pin "6") (pinfunction "CLK_6") (pintype "passive"))
    )
    (net (code "64") (name "/SWCLK") (class "Default")
      (node (ref "P1") (pin "3") (pinfunction "3_3") (pintype "passive"))
      (node (ref "U1") (pin "76") (pinfunction "PA14/JTCK/SWCLK_76") (pintype "passive"))
    )
    (net (code "65") (name "/SWDIO") (class "Default")
      (node (ref "P1") (pin "4") (pinfunction "4_4") (pintype "passive"))
      (node (ref "U1") (pin "72") (pinfunction "PA13/JTMS/SWDIO_72") (pintype "passive"))
    )
    (net (code "66") (name "/TOUCH_SCL") (class "Default")
      (node (ref "P2") (pin "32") (pinfunction "32_32") (pintype "passive"))
      (node (ref "R21") (pin "1") (pinfunction "1_1") (pintype "passive"))
      (node (ref "U1") (pin "35") (pinfunction "PB0/ADC123_IN8/T3C3/T8C2N/T1C2N_35") (pintype "passive"))
    )
    (net (code "67") (name "/TOUCH_SDA") (class "Default")
      (node (ref "P2") (pin "33") (pinfunction "33_33") (pintype "passive"))
      (node (ref "R20") (pin "1") (pinfunction "1_1") (pintype "passive"))
      (node (ref "U1") (pin "36") (pinfunction "PB1/ADC123_IN9/T3C4/T8C3N/T1C3N_36") (pintype "passive"))
    )
    (net (code "68") (name "/UART4_RX") (class "Default")
      (node (ref "P6") (pin "5") (pinfunction "5_5") (pintype "passive"))
      (node (ref "U1") (pin "79") (pinfunction "PC11/UART4_Rx/SDIO_D3_79") (pintype "passive"))
    )
    (net (code "69") (name "/UART4_TX") (class "Default")
      (node (ref "P6") (pin "4") (pinfunction "4_4") (pintype "passive"))
      (node (ref "U1") (pin "78") (pinfunction "PC10/UART4_Tx/SDIO_D2_78") (pintype "passive"))
    )
    (net (code "70") (name "/USART2_RX") (class "Default")
      (node (ref "M1") (pin "16") (pinfunction "TXD0_16") (pintype "passive"))
      (node (ref "U1") (pin "26") (pinfunction "PA3/ADC123_IN3/USART2_Rx/T5C4/T2C4_26") (pintype "passive"))
    )
    (net (code "71") (name "/USART2_TX") (class "Default")
      (node (ref "M1") (pin "15") (pinfunction "RXD0_15") (pintype "passive"))
      (node (ref "U1") (pin "25") (pinfunction "PA2/ADC123_IN2/USART2_Tx/T5C3/T2C3_25") (pintype "passive"))
    )
    (net (code "72") (name "/USART3_RX") (class "Default")
      (node (ref "CON1") (pin "1") (pinfunction "TX_1") (pintype "passive"))
      (node (ref "P7") (pin "5") (pinfunction "5_5") (pintype "passive"))
      (node (ref "U1") (pin "48") (pinfunction "PB11/USART3_Rx/I2C2_SDA/T2C4_48") (pintype "passive"))
    )
    (net (code "73") (name "/USART3_TX") (class "Default")
      (node (ref "CON1") (pin "3") (pinfunction "RX_3") (pintype "passive"))
      (node (ref "P7") (pin "4") (pinfunction "4_4") (pintype "passive"))
      (node (ref "U1") (pin "47") (pinfunction "PB10/USART3_Tx/I2C2_SCL/T2C3_47") (pintype "passive"))
    )
    (net (code "74") (name "/USART6_RX") (class "Default")
      (node (ref "P8") (pin "2") (pinfunction "2_2") (pintype "passive"))
      (node (ref "U1") (pin "64") (pinfunction "PC7/I2S3_MCK/T8C2/T3C2/SDIO_D7_64") (pintype "passive"))
    )
    (net (code "75") (name "/USART6_TX") (class "Default")
      (node (ref "P8") (pin "3") (pinfunction "3_3") (pintype "passive"))
      (node (ref "U1") (pin "63") (pinfunction "PC6/I2S2_MCK/T8C1/T3C1/SDIO_D6_63") (pintype "passive"))
    )
    (net (code "76") (name "/VDDA") (class "Default")
      (node (ref "C25") (pin "1") (pinfunction "1_1") (pintype "passive"))
      (node (ref "C27") (pin "1") (pinfunction "1_1") (pintype "passive"))
      (node (ref "L1") (pin "1") (pinfunction "1_1") (pintype "passive"))
      (node (ref "R15") (pin "1") (pinfunction "1_1") (pintype "passive"))
      (node (ref "U1") (pin "22") (pinfunction "VDDA_22") (pintype "passive"))
    )
    (net (code "77") (name "/VREF") (class "Default")
      (node (ref "C26") (pin "1") (pinfunction "1_1") (pintype "passive"))
      (node (ref "R15") (pin "2") (pinfunction "2_2") (pintype "passive"))
      (node (ref "U1") (pin "21") (pinfunction "VREF+_21") (pintype "passive"))
    )
    (net (code "78") (name "/VSSA") (class "Default")
      (node (ref "C25") (pin "2") (pinfunction "2_2") (pintype "passive"))
      (node (ref "C26") (pin "2") (pinfunction "2_2") (pintype "passive"))
      (node (ref "C27") (pin "2") (pinfunction "2_2") (pintype "passive"))
      (node (ref "R14") (pin "2") (pinfunction "2_2") (pintype "passive"))
      (node (ref "U1") (pin "20") (pinfunction "VSSA_20") (pintype "passive"))
    )
    (net (code "79") (name "/WIFI_CTL") (class "Default")
      (node (ref "M1") (pin "3") (pinfunction "EN_3") (pintype "passive"))
      (node (ref "U1") (pin "15") (pinfunction "PC0/ADC123_IN10_15") (pintype "passive"))
    )
    (net (code "80") (name "3.3V") (class "Default")
      (node (ref "C11") (pin "1") (pinfunction "1_1") (pintype "passive"))
      (node (ref "C13") (pin "2") (pinfunction "2_2") (pintype "passive"))
      (node (ref "C14") (pin "2") (pinfunction "2_2") (pintype "passive"))
      (node (ref "C15") (pin "2") (pinfunction "2_2") (pintype "passive"))
      (node (ref "C16") (pin "2") (pinfunction "2_2") (pintype "passive"))
      (node (ref "C17") (pin "2") (pinfunction "2_2") (pintype "passive"))
      (node (ref "C18") (pin "2") (pinfunction "2_2") (pintype "passive"))
      (node (ref "C19") (pin "2") (pinfunction "2_2") (pintype "passive"))
      (node (ref "C2") (pin "2") (pinfunction "2_2") (pintype "passive"))
      (node (ref "C24") (pin "2") (pinfunction "2_2") (pintype "passive"))
      (node (ref "D1") (pin "1") (pinfunction "A_1") (pintype "passive"))
      (node (ref "J1") (pin "1") (pinfunction "0_1") (pintype "passive"))
      (node (ref "L1") (pin "2") (pinfunction "2_2") (pintype "passive"))
      (node (ref "M1") (pin "8") (pinfunction "VCC_8") (pintype "passive"))
      (node (ref "M2") (pin "1") (pinfunction "VCC_1") (pintype "passive"))
      (node (ref "P1") (pin "5") (pinfunction "5_5") (pintype "passive"))
      (node (ref "P10") (pin "1") (pinfunction "1_1") (pintype "passive"))
      (node (ref "P5") (pin "4") (pinfunction "4_4") (pintype "passive"))
      (node (ref "P8") (pin "4") (pinfunction "4_4") (pintype "passive"))
      (node (ref "R26") (pin "2") (pinfunction "2_2") (pintype "passive"))
      (node (ref "R27") (pin "1") (pinfunction "1_1") (pintype "passive"))
      (node (ref "R4") (pin "1") (pinfunction "1_1") (pintype "passive"))
      (node (ref "R6") (pin "2") (pinfunction "2_2") (pintype "passive"))
      (node (ref "R7") (pin "2") (pinfunction "2_2") (pintype "passive"))
      (node (ref "U1") (pin "100") (pinfunction "VDD_3_100") (pintype "passive"))
      (node (ref "U1") (pin "11") (pinfunction "VDD_5_11") (pintype "passive"))
      (node (ref "U1") (pin "19") (pinfunction "VDD12_19") (pintype "passive"))
      (node (ref "U1") (pin "28") (pinfunction "VDD_4_28") (pintype "passive"))
      (node (ref "U1") (pin "50") (pinfunction "VDD_1_50") (pintype "passive"))
      (node (ref "U1") (pin "75") (pinfunction "VDD_2_75") (pintype "passive"))
      (node (ref "U5") (pin "3") (pinfunction "~{WP}_3") (pintype "passive"))
      (node (ref "U5") (pin "7") (pinfunction "~{HOLD}_7") (pintype "passive"))
      (node (ref "U5") (pin "8") (pinfunction "VCC_8") (pintype "passive"))
      (node (ref "U6") (pin "2") (pinfunction "OUT_2") (pintype "passive"))
      (node (ref "U6") (pin "4") (pinfunction "OUT_4") (pintype "passive"))
    )
    (net (code "81") (name "3.3V_2") (class "Default")
      (node (ref "C21") (pin "1") (pinfunction "1_1") (pintype "passive"))
      (node (ref "C23") (pin "2") (pinfunction "2_2") (pintype "passive"))
      (node (ref "P2") (pin "40") (pinfunction "40_40") (pintype "passive"))
      (node (ref "R20") (pin "2") (pinfunction "2_2") (pintype "passive"))
      (node (ref "R21") (pin "2") (pinfunction "2_2") (pintype "passive"))
      (node (ref "R22") (pin "2") (pinfunction "2_2") (pintype "passive"))
      (node (ref "R23") (pin "2") (pinfunction "2_2") (pintype "passive"))
      (node (ref "U2") (pin "2") (pinfunction "OUT_2") (pintype "passive"))
      (node (ref "U2") (pin "4") (pinfunction "OUT_4") (pintype "passive"))
    )
    (net (code "82") (name "5V") (class "Default")
      (node (ref "C10") (pin "1") (pinfunction "1_1") (pintype "passive"))
      (node (ref "C12") (pin "2") (pinfunction "2_2") (pintype "passive"))
      (node (ref "C20") (pin "1") (pinfunction "1_1") (pintype "passive"))
      (node (ref "C22") (pin "2") (pinfunction "2_2") (pintype "passive"))
      (node (ref "C28") (pin "1") (pinfunction "1_1") (pintype "passive"))
      (node (ref "C29") (pin "2") (pinfunction "2_2") (pintype "passive"))
      (node (ref "CON1") (pin "0") (pinfunction "Vcc_0") (pintype "passive"))
      (node (ref "P11") (pin "3") (pinfunction "3_3") (pintype "passive"))
      (node (ref "P6") (pin "2") (pinfunction "2_2") (pintype "passive"))
      (node (ref "P7") (pin "1") (pinfunction "1_1") (pintype "passive"))
      (node (ref "P9") (pin "1") (pinfunction "VCC_1") (pintype "passive"))
      (node (ref "Q3") (pin "2") (pinfunction "S_2") (pintype "passive"))
      (node (ref "R24") (pin "2") (pinfunction "2_2") (pintype "passive"))
      (node (ref "R5") (pin "2") (pinfunction "2_2") (pintype "passive"))
      (node (ref "U2") (pin "3") (pinfunction "IN_3") (pintype "passive"))
      (node (ref "U6") (pin "3") (pinfunction "IN_3") (pintype "passive"))
    )
    (net (code "83") (name "GND") (class "Default")
      (node (ref "BT1") (pin "2") (pinfunction "-_2") (pintype "passive"))
      (node (ref "C1") (pin "2") (pinfunction "2_2") (pintype "passive"))
      (node (ref "C10") (pin "2") (pinfunction "2_2") (pintype "passive"))
      (node (ref "C11") (pin "2") (pinfunction "2_2") (pintype "passive"))
      (node (ref "C12") (pin "1") (pinfunction "1_1") (pintype "passive"))
      (node (ref "C13") (pin "1") (pinfunction "1_1") (pintype "passive"))
      (node (ref "C14") (pin "1") (pinfunction "1_1") (pintype "passive"))
      (node (ref "C15") (pin "1") (pinfunction "1_1") (pintype "passive"))
      (node (ref "C16") (pin "1") (pinfunction "1_1") (pintype "passive"))
      (node (ref "C17") (pin "1") (pinfunction "1_1") (pintype "passive"))
      (node (ref "C18") (pin "1") (pinfunction "1_1") (pintype "passive"))
      (node (ref "C19") (pin "1") (pinfunction "1_1") (pintype "passive"))
      (node (ref "C2") (pin "1") (pinfunction "1_1") (pintype "passive"))
      (node (ref "C20") (pin "2") (pinfunction "2_2") (pintype "passive"))
      (node (ref "C21") (pin "2") (pinfunction "2_2") (pintype "passive"))
      (node (ref "C22") (pin "1") (pinfunction "1_1") (pintype "passive"))
      (node (ref "C23") (pin "1") (pinfunction "1_1") (pintype "passive"))
      (node (ref "C24") (pin "1") (pinfunction "1_1") (pintype "passive"))
      (node (ref "C28") (pin "2") (pinfunction "2_2") (pintype "passive"))
      (node (ref "C29") (pin "1") (pinfunction "1_1") (pintype "passive"))
      (node (ref "C3") (pin "2") (pinfunction "2_2") (pintype "passive"))
      (node (ref "C4") (pin "2") (pinfunction "2_2") (pintype "passive"))
      (node (ref "C5") (pin "1") (pinfunction "1_1") (pintype "passive"))
      (node (ref "C6") (pin "1") (pinfunction "1_1") (pintype "passive"))
      (node (ref "C8") (pin "1") (pinfunction "1_1") (pintype "passive"))
      (node (ref "C9") (pin "1") (pinfunction "1_1") (pintype "passive"))
      (node (ref "CON1") (pin "4") (pinfunction "GND_4") (pintype "passive"))
      (node (ref "D3") (pin "2") (pinfunction "K_2") (pintype "passive"))
      (node (ref "D4") (pin "2") (pinfunction "K_2") (pintype "passive"))
      (node (ref "D5") (pin "2") (pinfunction "K_2") (pintype "passive"))
      (node (ref "M1") (pin "17") (pinfunction "GND_17") (pintype "passive"))
      (node (ref "M1") (pin "9") (pinfunction "GND_9") (pintype "passive"))
      (node (ref "M2") (pin "8") (pinfunction "GND_8") (pintype "passive"))
      (node (ref "P1") (pin "2") (pinfunction "2_2") (pintype "passive"))
      (node (ref "P10") (pin "2") (pinfunction "2_2") (pintype "passive"))
      (node (ref "P11") (pin "1") (pinfunction "1_1") (pintype "passive"))
      (node (ref "P2") (pin "2") (pinfunction "2_2") (pintype "passive"))
      (node (ref "P2") (pin "39") (pinfunction "39_39") (pintype "passive"))
      (node (ref "P3") (pin "2") (pinfunction "2_2") (pintype "passive"))
      (node (ref "P5") (pin "2") (pinfunction "2_2") (pintype "passive"))
      (node (ref "P6") (pin "3") (pinfunction "3_3") (pintype "passive"))
      (node (ref "P7") (pin "2") (pinfunction "2_2") (pintype "passive"))
      (node (ref "P8") (pin "1") (pinfunction "1_1") (pintype "passive"))
      (node (ref "P9") (pin "5") (pinfunction "VSS_5") (pintype "passive"))
      (node (ref "Q1") (pin "2") (pinfunction "E_2") (pintype "passive"))
      (node (ref "Q2") (pin "2") (pinfunction "E_2") (pintype "passive"))
      (node (ref "R1") (pin "1") (pinfunction "1_1") (pintype "passive"))
      (node (ref "R13") (pin "1") (pinfunction "1_1") (pintype "passive"))
      (node (ref "R14") (pin "1") (pinfunction "1_1") (pintype "passive"))
      (node (ref "R2") (pin "1") (pinfunction "1_1") (pintype "passive"))
      (node (ref "U1") (pin "10") (pinfunction "VSS_5_10") (pintype "passive"))
      (node (ref "U1") (pin "27") (pinfunction "VSS_4_27") (pintype "passive"))
      (node (ref "U1") (pin "74") (pinfunction "VSS_2_74") (pintype "passive"))
      (node (ref "U2") (pin "1") (pinfunction "GND_1") (pintype "passive"))
      (node (ref "U5") (pin "4") (pinfunction "GND_4") (pintype "passive"))
      (node (ref "U6") (pin "1") (pinfunction "GND_1") (pintype "passive"))
    )
    (net (code "84") (name "Net-(BT1-+)") (class "Default")
      (node (ref "BT1") (pin "1") (pinfunction "+_1") (pintype "passive"))
      (node (ref "D6") (pin "1") (pinfunction "A_1") (pintype "passive"))
    )
    (net (code "85") (name "Net-(D1-K)") (class "Default")
      (node (ref "D1") (pin "2") (pinfunction "K_2") (pintype "passive"))
      (node (ref "D6") (pin "2") (pinfunction "K_2") (pintype "passive"))
      (node (ref "U1") (pin "6") (pinfunction "VBAT_6") (pintype "passive"))
    )
    (net (code "86") (name "Net-(D3-A)") (class "Default")
      (node (ref "D3") (pin "1") (pinfunction "A_1") (pintype "passive"))
      (node (ref "R5") (pin "1") (pinfunction "1_1") (pintype "passive"))
    )
    (net (code "87") (name "Net-(D4-A)") (class "Default")
      (node (ref "D4") (pin "1") (pinfunction "A_1") (pintype "passive"))
      (node (ref "R16") (pin "1") (pinfunction "1_1") (pintype "passive"))
    )
    (net (code "88") (name "Net-(D5-A)") (class "Default")
      (node (ref "D5") (pin "1") (pinfunction "A_1") (pintype "passive"))
      (node (ref "R17") (pin "1") (pinfunction "1_1") (pintype "passive"))
    )
    (net (code "89") (name "Net-(J1-1)") (class "Default")
      (node (ref "J1") (pin "2") (pinfunction "1_2") (pintype "passive"))
      (node (ref "Q1") (pin "3") (pinfunction "C_3") (pintype "passive"))
    )
    (net (code "90") (name "Net-(Q1-B)") (class "Default")
      (node (ref "Q1") (pin "1") (pinfunction "B_1") (pintype "passive"))
      (node (ref "R9") (pin "1") (pinfunction "1_1") (pintype "passive"))
    )
    (net (code "91") (name "Net-(Q2-B)") (class "Default")
      (node (ref "Q2") (pin "1") (pinfunction "B_1") (pintype "passive"))
      (node (ref "R25") (pin "1") (pinfunction "1_1") (pintype "passive"))
    )
    (net (code "92") (name "Net-(Q2-C)") (class "Default")
      (node (ref "Q2") (pin "3") (pinfunction "C_3") (pintype "passive"))
      (node (ref "Q3") (pin "1") (pinfunction "G_1") (pintype "passive"))
      (node (ref "R24") (pin "1") (pinfunction "1_1") (pintype "passive"))
    )
    (net (code "93") (name "Net-(U1A-PB2{slash}BOOT1)") (class "Default")
      (node (ref "R2") (pin "2") (pinfunction "2_2") (pintype "passive"))
      (node (ref "U1") (pin "37") (pinfunction "PB2/BOOT1_37") (pintype "passive"))
    )
    (net (code "94") (name "Net-(U1A-PD13{slash}T4C2{slash}FSMC_A18)") (class "Default")
      (node (ref "R28") (pin "1") (pinfunction "1_1") (pintype "passive"))
      (node (ref "U1") (pin "60") (pinfunction "PD13/T4C2/FSMC_A18_60") (pintype "passive"))
    )
    (net (code "95") (name "Net-(U1B-BOOT0)") (class "Default")
      (node (ref "R1") (pin "2") (pinfunction "2_2") (pintype "passive"))
      (node (ref "U1") (pin "94") (pinfunction "BOOT0_94") (pintype "passive"))
    )
    (net (code "96") (name "Net-(U1B-NRST)") (class "Default")
      (node (ref "C1") (pin "1") (pinfunction "1_1") (pintype "passive"))
      (node (ref "U1") (pin "14") (pinfunction "NRST_14") (pintype "passive"))
    )
    (net (code "97") (name "Net-(U1B-OSC_IN)") (class "Default")
      (node (ref "C8") (pin "2") (pinfunction "2_2") (pintype "passive"))
      (node (ref "U1") (pin "12") (pinfunction "OSC_IN_12") (pintype "passive"))
      (node (ref "Y1") (pin "2") (pinfunction "OSC2_2") (pintype "passive"))
    )
    (net (code "98") (name "Net-(U1B-OSC_OUT)") (class "Default")
      (node (ref "C9") (pin "2") (pinfunction "2_2") (pintype "passive"))
      (node (ref "U1") (pin "13") (pinfunction "OSC_OUT_13") (pintype "passive"))
      (node (ref "Y1") (pin "1") (pinfunction "OSC1_1") (pintype "passive"))
    )
    (net (code "99") (name "Net-(U1B-PDR_ON)") (class "Default")
      (node (ref "R4") (pin "2") (pinfunction "2_2") (pintype "passive"))
      (node (ref "U1") (pin "99") (pinfunction "PDR_ON_99") (pintype "passive"))
    )
    (net (code "100") (name "Net-(U1B-VCAP1)") (class "Default")
      (node (ref "C4") (pin "1") (pinfunction "1_1") (pintype "passive"))
      (node (ref "U1") (pin "49") (pinfunction "VCAP1_49") (pintype "passive"))
    )
    (net (code "101") (name "Net-(U1B-VCAP2)") (class "Default")
      (node (ref "C3") (pin "1") (pinfunction "1_1") (pintype "passive"))
      (node (ref "U1") (pin "73") (pinfunction "VCAP2_73") (pintype "passive"))
    )
    (net (code "102") (name "unconnected-(M1-ADC-Pad2)") (class "Default")
      (node (ref "M1") (pin "2") (pinfunction "ADC_2") (pintype "passive+no_connect"))
    )
    (net (code "103") (name "unconnected-(M1-IO0-Pad12)") (class "Default")
      (node (ref "M1") (pin "12") (pinfunction "IO0_12") (pintype "passive+no_connect"))
    )
    (net (code "104") (name "unconnected-(M1-IO2-Pad11)") (class "Default")
      (node (ref "M1") (pin "11") (pinfunction "IO2_11") (pintype "passive+no_connect"))
    )
    (net (code "105") (name "unconnected-(M1-IO4-Pad13)") (class "Default")
      (node (ref "M1") (pin "13") (pinfunction "IO4_13") (pintype "passive+no_connect"))
    )
    (net (code "106") (name "unconnected-(M1-IO5-Pad14)") (class "Default")
      (node (ref "M1") (pin "14") (pinfunction "IO5_14") (pintype "passive+no_connect"))
    )
    (net (code "107") (name "unconnected-(M1-IO12-Pad6)") (class "Default")
      (node (ref "M1") (pin "6") (pinfunction "IO12_6") (pintype "passive+no_connect"))
    )
    (net (code "108") (name "unconnected-(M1-IO13-Pad7)") (class "Default")
      (node (ref "M1") (pin "7") (pinfunction "IO13_7") (pintype "passive+no_connect"))
    )
    (net (code "109") (name "unconnected-(M1-IO13-Pad10)") (class "Default")
      (node (ref "M1") (pin "10") (pinfunction "IO13_10") (pintype "passive+no_connect"))
    )
    (net (code "110") (name "unconnected-(M1-IO14-Pad5)") (class "Default")
      (node (ref "M1") (pin "5") (pinfunction "IO14_5") (pintype "passive+no_connect"))
    )
    (net (code "111") (name "unconnected-(M1-IO16-Pad4)") (class "Default")
      (node (ref "M1") (pin "4") (pinfunction "IO16_4") (pintype "passive+no_connect"))
    )
    (net (code "112") (name "unconnected-(M1-RST-Pad1)") (class "Default")
      (node (ref "M1") (pin "1") (pinfunction "RST_1") (pintype "passive+no_connect"))
    )
    (net (code "113") (name "unconnected-(P2-Pad1)") (class "Default")
      (node (ref "P2") (pin "1") (pinfunction "1_1") (pintype "passive+no_connect"))
    )
    (net (code "114") (name "unconnected-(P2-Pad3)") (class "Default")
      (node (ref "P2") (pin "3") (pinfunction "3_3") (pintype "passive+no_connect"))
    )
    (net (code "115") (name "unconnected-(P2-Pad4)") (class "Default")
      (node (ref "P2") (pin "4") (pinfunction "4_4") (pintype "passive+no_connect"))
    )
    (net (code "116") (name "unconnected-(P2-Pad5)") (class "Default")
      (node (ref "P2") (pin "5") (pinfunction "5_5") (pintype "passive+no_connect"))
    )
    (net (code "117") (name "unconnected-(P2-Pad6)") (class "Default")
      (node (ref "P2") (pin "6") (pinfunction "6_6") (pintype "passive+no_connect"))
    )
    (net (code "118") (name "unconnected-(P2-Pad7)") (class "Default")
      (node (ref "P2") (pin "7") (pinfunction "7_7") (pintype "passive+no_connect"))
    )
    (net (code "119") (name "unconnected-(P2-Pad8)") (class "Default")
      (node (ref "P2") (pin "8") (pinfunction "8_8") (pintype "passive+no_connect"))
    )
    (net (code "120") (name "unconnected-(P2-Pad9)") (class "Default")
      (node (ref "P2") (pin "9") (pinfunction "9_9") (pintype "passive+no_connect"))
    )
    (net (code "121") (name "unconnected-(P2-Pad10)") (class "Default")
      (node (ref "P2") (pin "10") (pinfunction "10_10") (pintype "passive+no_connect"))
    )
    (net (code "122") (name "unconnected-(P2-Pad34)") (class "Default")
      (node (ref "P2") (pin "34") (pinfunction "34_34") (pintype "passive+no_connect"))
    )
    (net (code "123") (name "unconnected-(P2-Pad35)") (class "Default")
      (node (ref "P2") (pin "35") (pinfunction "35_35") (pintype "passive+no_connect"))
    )
    (net (code "124") (name "unconnected-(P2-Pad36)") (class "Default")
      (node (ref "P2") (pin "36") (pinfunction "36_36") (pintype "passive+no_connect"))
    )
    (net (code "125") (name "unconnected-(P3-Pad3)") (class "Default")
      (node (ref "P3") (pin "3") (pinfunction "3_3") (pintype "passive+no_connect"))
    )
    (net (code "126") (name "unconnected-(P6-Pad1)") (class "Default")
      (node (ref "P6") (pin "1") (pinfunction "1_1") (pintype "passive+no_connect"))
    )
    (net (code "127") (name "unconnected-(P9-D+-Pad3)") (class "Default")
      (node (ref "P9") (pin "3") (pinfunction "D+_3") (pintype "passive+no_connect"))
    )
    (net (code "128") (name "unconnected-(P9-D--Pad2)") (class "Default")
      (node (ref "P9") (pin "2") (pinfunction "D-_2") (pintype "passive+no_connect"))
    )
    (net (code "129") (name "unconnected-(P9-ID-Pad4)") (class "Default")
      (node (ref "P9") (pin "4") (pinfunction "ID_4") (pintype "passive+no_connect"))
    )
    (net (code "130") (name "unconnected-(U1A-PA1{slash}ADC123_IN1{slash}T5C2{slash}T2C2-Pad24)") (class "Default")
      (node (ref "U1") (pin "24") (pinfunction "PA1/ADC123_IN1/T5C2/T2C2_24") (pintype "passive"))
    )
    (net (code "131") (name "unconnected-(U1A-PA5{slash}ADC123_IN5{slash}DAC_OUT2{slash}SPI1_SCK-Pad30)") (class "Default")
      (node (ref "U1") (pin "30") (pinfunction "PA5/ADC123_IN5/DAC_OUT2/SPI1_SCK_30") (pintype "passive"))
    )
    (net (code "132") (name "unconnected-(U1A-PC1{slash}ADC123_IN11-Pad16)") (class "Default")
      (node (ref "U1") (pin "16") (pinfunction "PC1/ADC123_IN11_16") (pintype "passive"))
    )
    (net (code "133") (name "unconnected-(U1A-PC4{slash}ADC123_IN14-Pad33)") (class "Default")
      (node (ref "U1") (pin "33") (pinfunction "PC4/ADC123_IN14_33") (pintype "passive"))
    )
    (net (code "134") (name "unconnected-(U1A-PC12{slash}UART5_Tx{slash}SDIO_CK-Pad80)") (class "Default")
      (node (ref "U1") (pin "80") (pinfunction "PC12/UART5_Tx/SDIO_CK_80") (pintype "passive"))
    )
    (net (code "135") (name "unconnected-(U1A-PC13-TAMPER-RTC-Pad7)") (class "Default")
      (node (ref "U1") (pin "7") (pinfunction "PC13-TAMPER-RTC_7") (pintype "passive"))
    )
  )
)
